# AirHarp_Pico_1_001.net
KiCad netlist of a schematic drawn in EAGLE
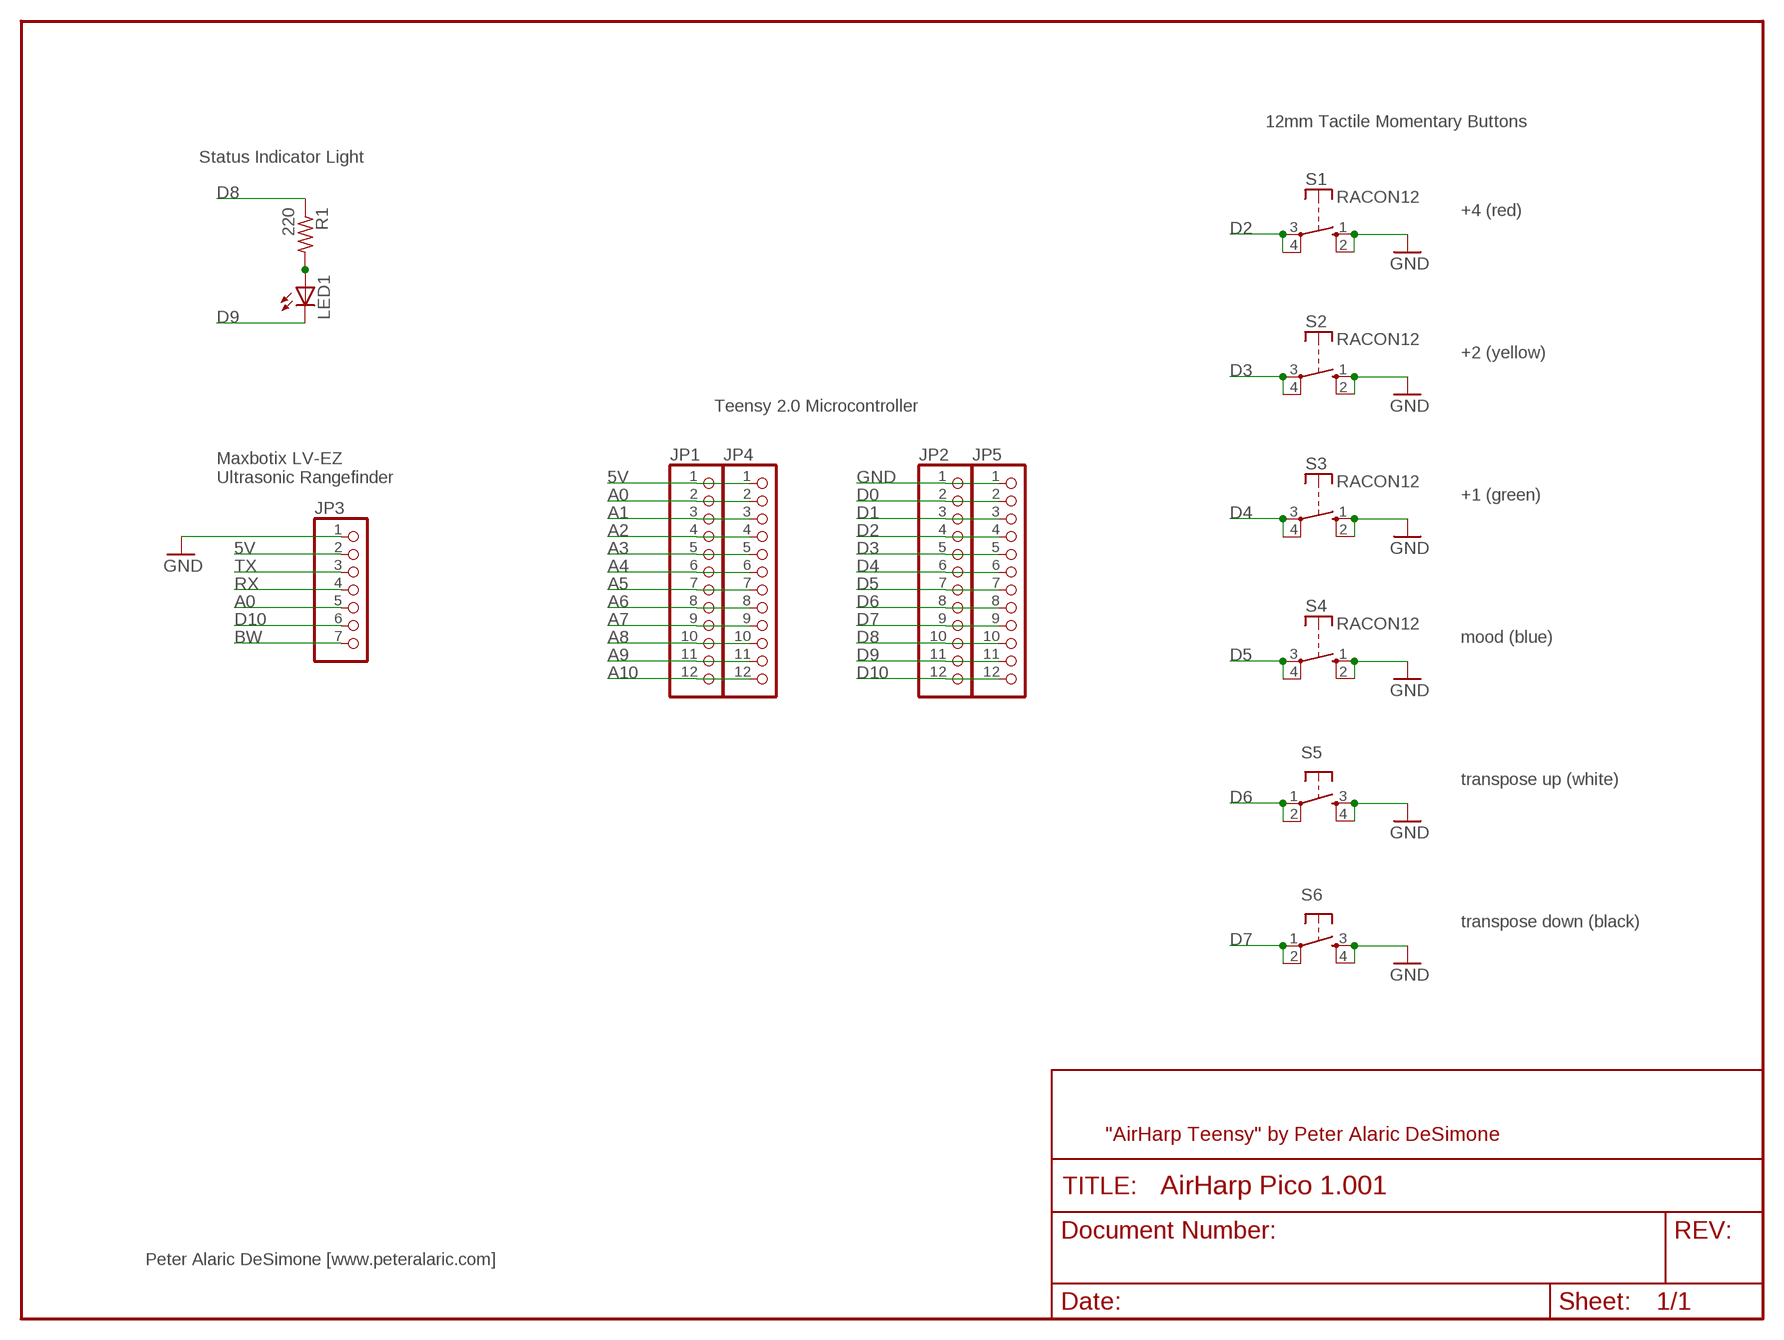
[diagram p0: schematic, sheet 1]

(export (version "E")
  (design (tool "Eeschema 10.0.6"))
  (components
    (comp (ref "JP1")
      (value "PINHD-1X12")
      (footprint "eagle-import:1X12")
      (libsource (lib "eagle-import") (part "PINHD-1X12"))
    )
    (comp (ref "JP2")
      (value "PINHD-1X12")
      (footprint "eagle-import:1X12")
      (libsource (lib "eagle-import") (part "PINHD-1X12"))
    )
    (comp (ref "JP3")
      (value "PINHD-1X7")
      (footprint "eagle-import:1X07")
      (libsource (lib "eagle-import") (part "PINHD-1X7"))
    )
    (comp (ref "JP4")
      (value "PINHD-1X12")
      (footprint "eagle-import:1X12")
      (libsource (lib "eagle-import") (part "PINHD-1X12"))
    )
    (comp (ref "JP5")
      (value "PINHD-1X12")
      (footprint "eagle-import:1X12")
      (libsource (lib "eagle-import") (part "PINHD-1X12"))
    )
    (comp (ref "LED1")
      (value "LED10MM")
      (footprint "eagle-import:LED10MM")
      (libsource (lib "eagle-import") (part "LED10MM"))
    )
    (comp (ref "R1")
      (value "220")
      (footprint "eagle-import:0207_7")
      (libsource (lib "eagle-import") (part "R-US_0207/7"))
    )
    (comp (ref "S1")
      (value "RACON12")
      (footprint "eagle-import:RACON12")
      (libsource (lib "eagle-import") (part "RACON12"))
    )
    (comp (ref "S2")
      (value "RACON12")
      (footprint "eagle-import:RACON12")
      (libsource (lib "eagle-import") (part "RACON12"))
    )
    (comp (ref "S3")
      (value "RACON12")
      (footprint "eagle-import:RACON12")
      (libsource (lib "eagle-import") (part "RACON12"))
    )
    (comp (ref "S4")
      (value "RACON12")
      (footprint "eagle-import:RACON12")
      (libsource (lib "eagle-import") (part "RACON12"))
    )
    (comp (ref "S5")
      (value "TAC_SWITCHPTH")
      (footprint "eagle-import:TACTILE-PTH")
      (libsource (lib "eagle-import") (part "TAC_SWITCHPTH"))
    )
    (comp (ref "S6")
      (value "TAC_SWITCHPTH")
      (footprint "eagle-import:TACTILE-PTH")
      (libsource (lib "eagle-import") (part "TAC_SWITCHPTH"))
    )
  )
  (nets
    (net (code "1") (name "/5V") (class "Default")
      (node (ref "JP1") (pin "1") (pinfunction "1_1") (pintype "passive"))
      (node (ref "JP3") (pin "2") (pinfunction "2_2") (pintype "passive"))
      (node (ref "JP4") (pin "1") (pinfunction "1_1") (pintype "passive"))
    )
    (net (code "2") (name "/A0") (class "Default")
      (node (ref "JP1") (pin "2") (pinfunction "2_2") (pintype "passive"))
      (node (ref "JP3") (pin "5") (pinfunction "5_5") (pintype "passive"))
      (node (ref "JP4") (pin "2") (pinfunction "2_2") (pintype "passive"))
    )
    (net (code "3") (name "/A1") (class "Default")
      (node (ref "JP1") (pin "3") (pinfunction "3_3") (pintype "passive"))
      (node (ref "JP4") (pin "3") (pinfunction "3_3") (pintype "passive"))
    )
    (net (code "4") (name "/A2") (class "Default")
      (node (ref "JP1") (pin "4") (pinfunction "4_4") (pintype "passive"))
      (node (ref "JP4") (pin "4") (pinfunction "4_4") (pintype "passive"))
    )
    (net (code "5") (name "/A3") (class "Default")
      (node (ref "JP1") (pin "5") (pinfunction "5_5") (pintype "passive"))
      (node (ref "JP4") (pin "5") (pinfunction "5_5") (pintype "passive"))
    )
    (net (code "6") (name "/A4") (class "Default")
      (node (ref "JP1") (pin "6") (pinfunction "6_6") (pintype "passive"))
      (node (ref "JP4") (pin "6") (pinfunction "6_6") (pintype "passive"))
    )
    (net (code "7") (name "/A5") (class "Default")
      (node (ref "JP1") (pin "7") (pinfunction "7_7") (pintype "passive"))
      (node (ref "JP4") (pin "7") (pinfunction "7_7") (pintype "passive"))
    )
    (net (code "8") (name "/A6") (class "Default")
      (node (ref "JP1") (pin "8") (pinfunction "8_8") (pintype "passive"))
      (node (ref "JP4") (pin "8") (pinfunction "8_8") (pintype "passive"))
    )
    (net (code "9") (name "/A7") (class "Default")
      (node (ref "JP1") (pin "9") (pinfunction "9_9") (pintype "passive"))
      (node (ref "JP4") (pin "9") (pinfunction "9_9") (pintype "passive"))
    )
    (net (code "10") (name "/A8") (class "Default")
      (node (ref "JP1") (pin "10") (pinfunction "10_10") (pintype "passive"))
      (node (ref "JP4") (pin "10") (pinfunction "10_10") (pintype "passive"))
    )
    (net (code "11") (name "/A9") (class "Default")
      (node (ref "JP1") (pin "11") (pinfunction "11_11") (pintype "passive"))
      (node (ref "JP4") (pin "11") (pinfunction "11_11") (pintype "passive"))
    )
    (net (code "12") (name "/A10") (class "Default")
      (node (ref "JP1") (pin "12") (pinfunction "12_12") (pintype "passive"))
      (node (ref "JP4") (pin "12") (pinfunction "12_12") (pintype "passive"))
    )
    (net (code "13") (name "/BW") (class "Default")
      (node (ref "JP3") (pin "7") (pinfunction "7_7") (pintype "passive"))
    )
    (net (code "14") (name "/D0") (class "Default")
      (node (ref "JP2") (pin "2") (pinfunction "2_2") (pintype "passive"))
      (node (ref "JP5") (pin "2") (pinfunction "2_2") (pintype "passive"))
    )
    (net (code "15") (name "/D1") (class "Default")
      (node (ref "JP2") (pin "3") (pinfunction "3_3") (pintype "passive"))
      (node (ref "JP5") (pin "3") (pinfunction "3_3") (pintype "passive"))
    )
    (net (code "16") (name "/D2") (class "Default")
      (node (ref "JP2") (pin "4") (pinfunction "4_4") (pintype "passive"))
      (node (ref "JP5") (pin "4") (pinfunction "4_4") (pintype "passive"))
      (node (ref "S1") (pin "3") (pinfunction "P_3") (pintype "passive"))
      (node (ref "S1") (pin "4") (pinfunction "P_4") (pintype "passive"))
    )
    (net (code "17") (name "/D3") (class "Default")
      (node (ref "JP2") (pin "5") (pinfunction "5_5") (pintype "passive"))
      (node (ref "JP5") (pin "5") (pinfunction "5_5") (pintype "passive"))
      (node (ref "S2") (pin "3") (pinfunction "P_3") (pintype "passive"))
      (node (ref "S2") (pin "4") (pinfunction "P_4") (pintype "passive"))
    )
    (net (code "18") (name "/D4") (class "Default")
      (node (ref "JP2") (pin "6") (pinfunction "6_6") (pintype "passive"))
      (node (ref "JP5") (pin "6") (pinfunction "6_6") (pintype "passive"))
      (node (ref "S3") (pin "3") (pinfunction "P_3") (pintype "passive"))
      (node (ref "S3") (pin "4") (pinfunction "P_4") (pintype "passive"))
    )
    (net (code "19") (name "/D5") (class "Default")
      (node (ref "JP2") (pin "7") (pinfunction "7_7") (pintype "passive"))
      (node (ref "JP5") (pin "7") (pinfunction "7_7") (pintype "passive"))
      (node (ref "S4") (pin "3") (pinfunction "P_3") (pintype "passive"))
      (node (ref "S4") (pin "4") (pinfunction "P_4") (pintype "passive"))
    )
    (net (code "20") (name "/D6") (class "Default")
      (node (ref "JP2") (pin "8") (pinfunction "8_8") (pintype "passive"))
      (node (ref "JP5") (pin "8") (pinfunction "8_8") (pintype "passive"))
      (node (ref "S5") (pin "1") (pinfunction "1_1") (pintype "passive"))
      (node (ref "S5") (pin "2") (pinfunction "2_2") (pintype "passive"))
    )
    (net (code "21") (name "/D7") (class "Default")
      (node (ref "JP2") (pin "9") (pinfunction "9_9") (pintype "passive"))
      (node (ref "JP5") (pin "9") (pinfunction "9_9") (pintype "passive"))
      (node (ref "S6") (pin "1") (pinfunction "1_1") (pintype "passive"))
      (node (ref "S6") (pin "2") (pinfunction "2_2") (pintype "passive"))
    )
    (net (code "22") (name "/D8") (class "Default")
      (node (ref "JP2") (pin "10") (pinfunction "10_10") (pintype "passive"))
      (node (ref "JP5") (pin "10") (pinfunction "10_10") (pintype "passive"))
      (node (ref "R1") (pin "1") (pinfunction "1_1") (pintype "passive"))
    )
    (net (code "23") (name "/D9") (class "Default")
      (node (ref "JP2") (pin "11") (pinfunction "11_11") (pintype "passive"))
      (node (ref "JP5") (pin "11") (pinfunction "11_11") (pintype "passive"))
      (node (ref "LED1") (pin "K") (pinfunction "C_K") (pintype "passive"))
    )
    (net (code "24") (name "/D10") (class "Default")
      (node (ref "JP2") (pin "12") (pinfunction "12_12") (pintype "passive"))
      (node (ref "JP3") (pin "6") (pinfunction "6_6") (pintype "passive"))
      (node (ref "JP5") (pin "12") (pinfunction "12_12") (pintype "passive"))
    )
    (net (code "25") (name "/RX") (class "Default")
      (node (ref "JP3") (pin "4") (pinfunction "4_4") (pintype "passive"))
    )
    (net (code "26") (name "/TX") (class "Default")
      (node (ref "JP3") (pin "3") (pinfunction "3_3") (pintype "passive"))
    )
    (net (code "27") (name "GND") (class "Default")
      (node (ref "JP2") (pin "1") (pinfunction "1_1") (pintype "passive"))
      (node (ref "JP3") (pin "1") (pinfunction "1_1") (pintype "passive"))
      (node (ref "JP5") (pin "1") (pinfunction "1_1") (pintype "passive"))
      (node (ref "S1") (pin "1") (pinfunction "S_1") (pintype "passive"))
      (node (ref "S1") (pin "2") (pinfunction "S_2") (pintype "passive"))
      (node (ref "S2") (pin "1") (pinfunction "S_1") (pintype "passive"))
      (node (ref "S2") (pin "2") (pinfunction "S_2") (pintype "passive"))
      (node (ref "S3") (pin "1") (pinfunction "S_1") (pintype "passive"))
      (node (ref "S3") (pin "2") (pinfunction "S_2") (pintype "passive"))
      (node (ref "S4") (pin "1") (pinfunction "S_1") (pintype "passive"))
      (node (ref "S4") (pin "2") (pinfunction "S_2") (pintype "passive"))
      (node (ref "S5") (pin "3") (pinfunction "3_3") (pintype "passive"))
      (node (ref "S5") (pin "4") (pinfunction "4_4") (pintype "passive"))
      (node (ref "S6") (pin "3") (pinfunction "3_3") (pintype "passive"))
      (node (ref "S6") (pin "4") (pinfunction "4_4") (pintype "passive"))
    )
    (net (code "28") (name "Net-(LED1-PadA)") (class "Default")
      (node (ref "LED1") (pin "A") (pinfunction "A_A") (pintype "passive"))
      (node (ref "R1") (pin "2") (pinfunction "2_2") (pintype "passive"))
    )
  )
)
